# Comin_CTR_v_1_0.net
KiCad netlist of a schematic drawn in EAGLE
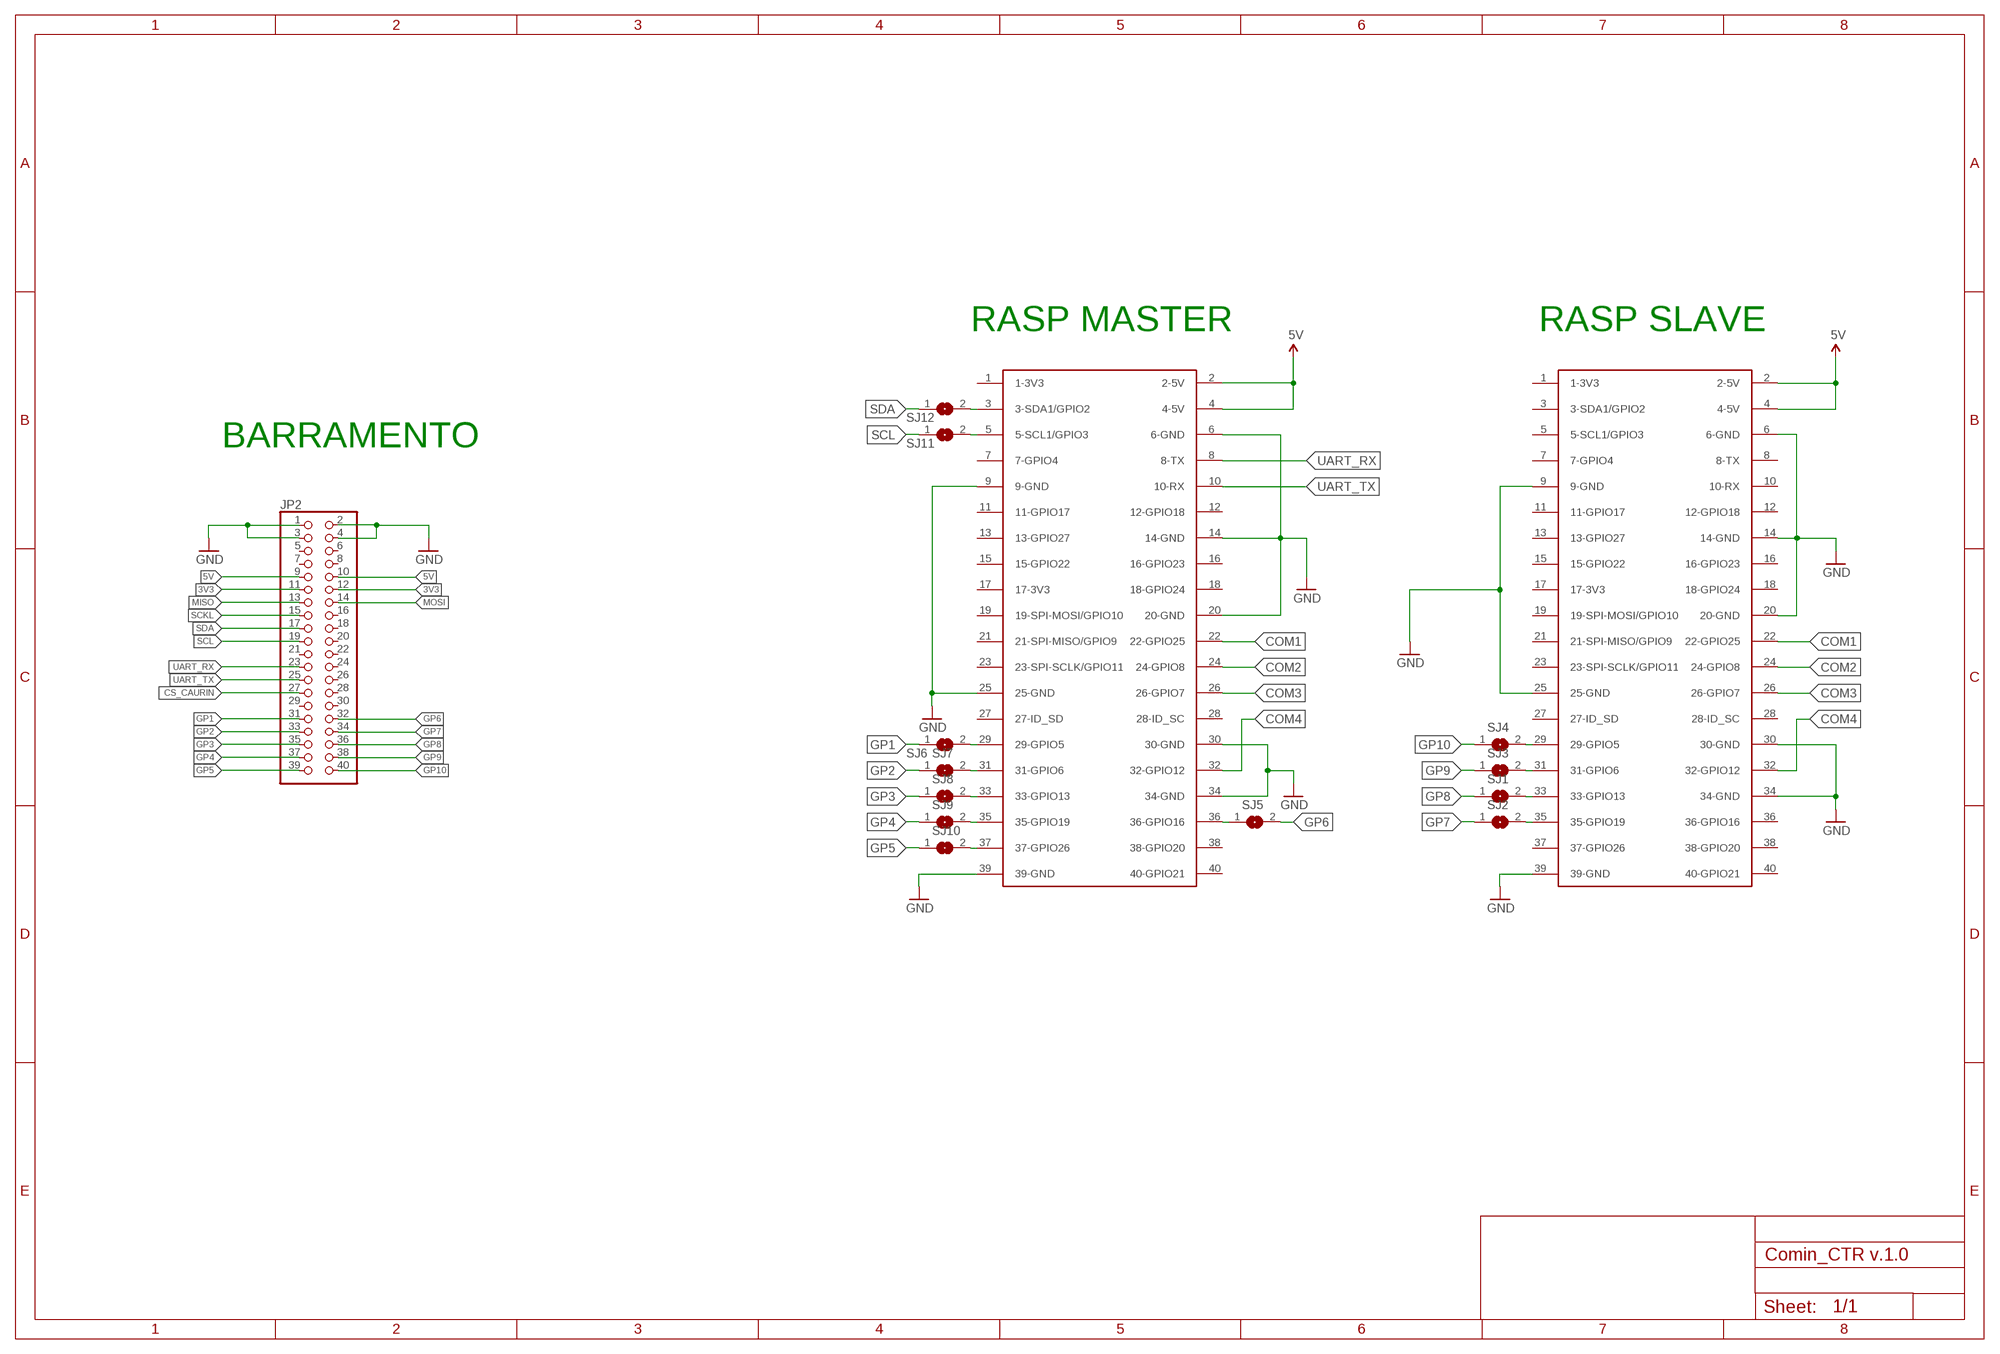
[diagram p0: schematic, sheet 1]

(export (version "E")
  (design (tool "Eeschema 10.0.6"))
  (components
    (comp (ref "JP2")
      (value "PINHD-2X20")
      (footprint "eagle-import:2X20")
      (libsource (lib "eagle-import") (part "PINHD-2X20"))
    )
    (comp (ref "SJ1") (value "SJ") (footprint "eagle-import:SJ") (libsource (lib "eagle-import") (part "SJ")))
    (comp (ref "SJ2") (value "SJ") (footprint "eagle-import:SJ") (libsource (lib "eagle-import") (part "SJ")))
    (comp (ref "SJ3") (value "SJ") (footprint "eagle-import:SJ") (libsource (lib "eagle-import") (part "SJ")))
    (comp (ref "SJ4") (value "SJ") (footprint "eagle-import:SJ") (libsource (lib "eagle-import") (part "SJ")))
    (comp (ref "SJ5") (value "SJ") (footprint "eagle-import:SJ") (libsource (lib "eagle-import") (part "SJ")))
    (comp (ref "SJ6") (value "SJ") (footprint "eagle-import:SJ") (libsource (lib "eagle-import") (part "SJ")))
    (comp (ref "SJ7") (value "SJ") (footprint "eagle-import:SJ") (libsource (lib "eagle-import") (part "SJ")))
    (comp (ref "SJ8") (value "SJ") (footprint "eagle-import:SJ") (libsource (lib "eagle-import") (part "SJ")))
    (comp (ref "SJ9") (value "SJ") (footprint "eagle-import:SJ") (libsource (lib "eagle-import") (part "SJ")))
    (comp (ref "SJ10")
      (value "SJ")
      (footprint "eagle-import:SJ")
      (libsource (lib "eagle-import") (part "SJ"))
    )
    (comp (ref "SJ11")
      (value "SJ")
      (footprint "eagle-import:SJ")
      (libsource (lib "eagle-import") (part "SJ"))
    )
    (comp (ref "SJ12")
      (value "SJ")
      (footprint "eagle-import:SJ")
      (libsource (lib "eagle-import") (part "SJ"))
    )
    (comp (ref "U$1")
      (value "RASPBERRY-PI+PIZERO")
      (footprint "eagle-import:RASPBERRY-PI-ZERO")
      (libsource (lib "eagle-import") (part "RASPBERRY-PI+PIZERO"))
    )
    (comp (ref "U$2")
      (value "RASPBERRY-PI+PIZERO")
      (footprint "eagle-import:RASPBERRY-PI-ZERO")
      (libsource (lib "eagle-import") (part "RASPBERRY-PI+PIZERO"))
    )
  )
  (nets
    (net (code "1") (name "3V3") (class "Default")
      (node (ref "JP2") (pin "11") (pinfunction "11_11") (pintype "passive"))
      (node (ref "JP2") (pin "12") (pinfunction "12_12") (pintype "passive"))
    )
    (net (code "2") (name "5V") (class "Default")
      (node (ref "JP2") (pin "10") (pinfunction "10_10") (pintype "passive"))
      (node (ref "JP2") (pin "9") (pinfunction "9_9") (pintype "passive"))
      (node (ref "U$1") (pin "2") (pinfunction "2-5V_2") (pintype "bidirectional"))
      (node (ref "U$1") (pin "4") (pinfunction "4-5V_4") (pintype "bidirectional"))
      (node (ref "U$2") (pin "2") (pinfunction "2-5V_2") (pintype "bidirectional"))
      (node (ref "U$2") (pin "4") (pinfunction "4-5V_4") (pintype "bidirectional"))
    )
    (net (code "3") (name "COM1") (class "Default")
      (node (ref "U$1") (pin "22") (pinfunction "22-GPIO25_22") (pintype "bidirectional"))
      (node (ref "U$2") (pin "22") (pinfunction "22-GPIO25_22") (pintype "bidirectional"))
    )
    (net (code "4") (name "COM2") (class "Default")
      (node (ref "U$1") (pin "24") (pinfunction "24-GPIO8_24") (pintype "bidirectional"))
      (node (ref "U$2") (pin "24") (pinfunction "24-GPIO8_24") (pintype "bidirectional"))
    )
    (net (code "5") (name "COM3") (class "Default")
      (node (ref "U$1") (pin "26") (pinfunction "26-GPIO7_26") (pintype "bidirectional"))
      (node (ref "U$2") (pin "26") (pinfunction "26-GPIO7_26") (pintype "bidirectional"))
    )
    (net (code "6") (name "COM4") (class "Default")
      (node (ref "U$1") (pin "32") (pinfunction "32-GPIO12_32") (pintype "bidirectional"))
      (node (ref "U$2") (pin "32") (pinfunction "32-GPIO12_32") (pintype "bidirectional"))
    )
    (net (code "7") (name "CS_CAURIN") (class "Default")
      (node (ref "JP2") (pin "27") (pinfunction "27_27") (pintype "passive"))
    )
    (net (code "8") (name "GND") (class "Default")
      (node (ref "JP2") (pin "1") (pinfunction "1_1") (pintype "passive"))
      (node (ref "JP2") (pin "2") (pinfunction "2_2") (pintype "passive"))
      (node (ref "JP2") (pin "3") (pinfunction "3_3") (pintype "passive"))
      (node (ref "JP2") (pin "4") (pinfunction "4_4") (pintype "passive"))
      (node (ref "U$1") (pin "14") (pinfunction "14-GND_14") (pintype "bidirectional"))
      (node (ref "U$1") (pin "20") (pinfunction "20-GND_20") (pintype "bidirectional"))
      (node (ref "U$1") (pin "25") (pinfunction "25-GND_25") (pintype "bidirectional"))
      (node (ref "U$1") (pin "30") (pinfunction "30-GND_30") (pintype "bidirectional"))
      (node (ref "U$1") (pin "34") (pinfunction "34-GND_34") (pintype "bidirectional"))
      (node (ref "U$1") (pin "39") (pinfunction "39-GND_39") (pintype "bidirectional"))
      (node (ref "U$1") (pin "6") (pinfunction "6-GND_6") (pintype "bidirectional"))
      (node (ref "U$1") (pin "9") (pinfunction "9-GND_9") (pintype "bidirectional"))
      (node (ref "U$2") (pin "14") (pinfunction "14-GND_14") (pintype "bidirectional"))
      (node (ref "U$2") (pin "20") (pinfunction "20-GND_20") (pintype "bidirectional"))
      (node (ref "U$2") (pin "25") (pinfunction "25-GND_25") (pintype "bidirectional"))
      (node (ref "U$2") (pin "30") (pinfunction "30-GND_30") (pintype "bidirectional"))
      (node (ref "U$2") (pin "34") (pinfunction "34-GND_34") (pintype "bidirectional"))
      (node (ref "U$2") (pin "39") (pinfunction "39-GND_39") (pintype "bidirectional"))
      (node (ref "U$2") (pin "6") (pinfunction "6-GND_6") (pintype "bidirectional"))
      (node (ref "U$2") (pin "9") (pinfunction "9-GND_9") (pintype "bidirectional"))
    )
    (net (code "9") (name "GP1") (class "Default")
      (node (ref "JP2") (pin "31") (pinfunction "31_31") (pintype "passive"))
      (node (ref "SJ6") (pin "1") (pinfunction "1_1") (pintype "passive"))
    )
    (net (code "10") (name "GP2") (class "Default")
      (node (ref "JP2") (pin "33") (pinfunction "33_33") (pintype "passive"))
      (node (ref "SJ7") (pin "1") (pinfunction "1_1") (pintype "passive"))
    )
    (net (code "11") (name "GP3") (class "Default")
      (node (ref "JP2") (pin "35") (pinfunction "35_35") (pintype "passive"))
      (node (ref "SJ8") (pin "1") (pinfunction "1_1") (pintype "passive"))
    )
    (net (code "12") (name "GP4") (class "Default")
      (node (ref "JP2") (pin "37") (pinfunction "37_37") (pintype "passive"))
      (node (ref "SJ9") (pin "1") (pinfunction "1_1") (pintype "passive"))
    )
    (net (code "13") (name "GP5") (class "Default")
      (node (ref "JP2") (pin "39") (pinfunction "39_39") (pintype "passive"))
      (node (ref "SJ10") (pin "1") (pinfunction "1_1") (pintype "passive"))
    )
    (net (code "14") (name "GP6") (class "Default")
      (node (ref "JP2") (pin "32") (pinfunction "32_32") (pintype "passive"))
      (node (ref "SJ5") (pin "2") (pinfunction "2_2") (pintype "passive"))
    )
    (net (code "15") (name "GP7") (class "Default")
      (node (ref "JP2") (pin "34") (pinfunction "34_34") (pintype "passive"))
      (node (ref "SJ2") (pin "1") (pinfunction "1_1") (pintype "passive"))
    )
    (net (code "16") (name "GP8") (class "Default")
      (node (ref "JP2") (pin "36") (pinfunction "36_36") (pintype "passive"))
      (node (ref "SJ1") (pin "1") (pinfunction "1_1") (pintype "passive"))
    )
    (net (code "17") (name "GP9") (class "Default")
      (node (ref "JP2") (pin "38") (pinfunction "38_38") (pintype "passive"))
      (node (ref "SJ3") (pin "1") (pinfunction "1_1") (pintype "passive"))
    )
    (net (code "18") (name "GP10") (class "Default")
      (node (ref "JP2") (pin "40") (pinfunction "40_40") (pintype "passive"))
      (node (ref "SJ4") (pin "1") (pinfunction "1_1") (pintype "passive"))
    )
    (net (code "19") (name "MISO") (class "Default")
      (node (ref "JP2") (pin "13") (pinfunction "13_13") (pintype "passive"))
    )
    (net (code "20") (name "MOSI") (class "Default")
      (node (ref "JP2") (pin "14") (pinfunction "14_14") (pintype "passive"))
    )
    (net (code "21") (name "Net-(U$1-29-GPIO5)") (class "Default")
      (node (ref "SJ4") (pin "2") (pinfunction "2_2") (pintype "passive"))
      (node (ref "U$1") (pin "29") (pinfunction "29-GPIO5_29") (pintype "bidirectional"))
    )
    (net (code "22") (name "Net-(U$1-31-GPIO6)") (class "Default")
      (node (ref "SJ3") (pin "2") (pinfunction "2_2") (pintype "passive"))
      (node (ref "U$1") (pin "31") (pinfunction "31-GPIO6_31") (pintype "bidirectional"))
    )
    (net (code "23") (name "Net-(U$1-33-GPIO13)") (class "Default")
      (node (ref "SJ1") (pin "2") (pinfunction "2_2") (pintype "passive"))
      (node (ref "U$1") (pin "33") (pinfunction "33-GPIO13_33") (pintype "bidirectional"))
    )
    (net (code "24") (name "Net-(U$1-35-GPIO19)") (class "Default")
      (node (ref "SJ2") (pin "2") (pinfunction "2_2") (pintype "passive"))
      (node (ref "U$1") (pin "35") (pinfunction "35-GPIO19_35") (pintype "bidirectional"))
    )
    (net (code "25") (name "Net-(U$2-3-SDA1{slash}GPIO2)") (class "Default")
      (node (ref "SJ12") (pin "2") (pinfunction "2_2") (pintype "passive"))
      (node (ref "U$2") (pin "3") (pinfunction "3-SDA1/GPIO2_3") (pintype "bidirectional"))
    )
    (net (code "26") (name "Net-(U$2-5-SCL1{slash}GPIO3)") (class "Default")
      (node (ref "SJ11") (pin "2") (pinfunction "2_2") (pintype "passive"))
      (node (ref "U$2") (pin "5") (pinfunction "5-SCL1/GPIO3_5") (pintype "bidirectional"))
    )
    (net (code "27") (name "Net-(U$2-29-GPIO5)") (class "Default")
      (node (ref "SJ6") (pin "2") (pinfunction "2_2") (pintype "passive"))
      (node (ref "U$2") (pin "29") (pinfunction "29-GPIO5_29") (pintype "bidirectional"))
    )
    (net (code "28") (name "Net-(U$2-31-GPIO6)") (class "Default")
      (node (ref "SJ7") (pin "2") (pinfunction "2_2") (pintype "passive"))
      (node (ref "U$2") (pin "31") (pinfunction "31-GPIO6_31") (pintype "bidirectional"))
    )
    (net (code "29") (name "Net-(U$2-33-GPIO13)") (class "Default")
      (node (ref "SJ8") (pin "2") (pinfunction "2_2") (pintype "passive"))
      (node (ref "U$2") (pin "33") (pinfunction "33-GPIO13_33") (pintype "bidirectional"))
    )
    (net (code "30") (name "Net-(U$2-35-GPIO19)") (class "Default")
      (node (ref "SJ9") (pin "2") (pinfunction "2_2") (pintype "passive"))
      (node (ref "U$2") (pin "35") (pinfunction "35-GPIO19_35") (pintype "bidirectional"))
    )
    (net (code "31") (name "Net-(U$2-36-GPIO16)") (class "Default")
      (node (ref "SJ5") (pin "1") (pinfunction "1_1") (pintype "passive"))
      (node (ref "U$2") (pin "36") (pinfunction "36-GPIO16_36") (pintype "bidirectional"))
    )
    (net (code "32") (name "Net-(U$2-37-GPIO26)") (class "Default")
      (node (ref "SJ10") (pin "2") (pinfunction "2_2") (pintype "passive"))
      (node (ref "U$2") (pin "37") (pinfunction "37-GPIO26_37") (pintype "bidirectional"))
    )
    (net (code "33") (name "SCKL") (class "Default")
      (node (ref "JP2") (pin "15") (pinfunction "15_15") (pintype "passive"))
    )
    (net (code "34") (name "SCL") (class "Default")
      (node (ref "JP2") (pin "19") (pinfunction "19_19") (pintype "passive"))
      (node (ref "SJ11") (pin "1") (pinfunction "1_1") (pintype "passive"))
    )
    (net (code "35") (name "SDA") (class "Default")
      (node (ref "JP2") (pin "17") (pinfunction "17_17") (pintype "passive"))
      (node (ref "SJ12") (pin "1") (pinfunction "1_1") (pintype "passive"))
    )
    (net (code "36") (name "UART_RX") (class "Default")
      (node (ref "JP2") (pin "23") (pinfunction "23_23") (pintype "passive"))
      (node (ref "U$2") (pin "8") (pinfunction "8-TX_8") (pintype "bidirectional"))
    )
    (net (code "37") (name "UART_TX") (class "Default")
      (node (ref "JP2") (pin "25") (pinfunction "25_25") (pintype "passive"))
      (node (ref "U$2") (pin "10") (pinfunction "10-RX_10") (pintype "bidirectional"))
    )
    (net (code "38") (name "unconnected-(JP2-Pad5)") (class "Default")
      (node (ref "JP2") (pin "5") (pinfunction "5_5") (pintype "passive"))
    )
    (net (code "39") (name "unconnected-(JP2-Pad6)") (class "Default")
      (node (ref "JP2") (pin "6") (pinfunction "6_6") (pintype "passive"))
    )
    (net (code "40") (name "unconnected-(JP2-Pad7)") (class "Default")
      (node (ref "JP2") (pin "7") (pinfunction "7_7") (pintype "passive"))
    )
    (net (code "41") (name "unconnected-(JP2-Pad8)") (class "Default")
      (node (ref "JP2") (pin "8") (pinfunction "8_8") (pintype "passive"))
    )
    (net (code "42") (name "unconnected-(JP2-Pad16)") (class "Default")
      (node (ref "JP2") (pin "16") (pinfunction "16_16") (pintype "passive"))
    )
    (net (code "43") (name "unconnected-(JP2-Pad18)") (class "Default")
      (node (ref "JP2") (pin "18") (pinfunction "18_18") (pintype "passive"))
    )
    (net (code "44") (name "unconnected-(JP2-Pad20)") (class "Default")
      (node (ref "JP2") (pin "20") (pinfunction "20_20") (pintype "passive"))
    )
    (net (code "45") (name "unconnected-(JP2-Pad21)") (class "Default")
      (node (ref "JP2") (pin "21") (pinfunction "21_21") (pintype "passive"))
    )
    (net (code "46") (name "unconnected-(JP2-Pad22)") (class "Default")
      (node (ref "JP2") (pin "22") (pinfunction "22_22") (pintype "passive"))
    )
    (net (code "47") (name "unconnected-(JP2-Pad24)") (class "Default")
      (node (ref "JP2") (pin "24") (pinfunction "24_24") (pintype "passive"))
    )
    (net (code "48") (name "unconnected-(JP2-Pad26)") (class "Default")
      (node (ref "JP2") (pin "26") (pinfunction "26_26") (pintype "passive"))
    )
    (net (code "49") (name "unconnected-(JP2-Pad28)") (class "Default")
      (node (ref "JP2") (pin "28") (pinfunction "28_28") (pintype "passive"))
    )
    (net (code "50") (name "unconnected-(JP2-Pad29)") (class "Default")
      (node (ref "JP2") (pin "29") (pinfunction "29_29") (pintype "passive"))
    )
    (net (code "51") (name "unconnected-(JP2-Pad30)") (class "Default")
      (node (ref "JP2") (pin "30") (pinfunction "30_30") (pintype "passive"))
    )
    (net (code "52") (name "unconnected-(U$1-1-3V3-Pad1)") (class "Default")
      (node (ref "U$1") (pin "1") (pinfunction "1-3V3_1") (pintype "bidirectional"))
    )
    (net (code "53") (name "unconnected-(U$1-3-SDA1{slash}GPIO2-Pad3)") (class "Default")
      (node (ref "U$1") (pin "3") (pinfunction "3-SDA1/GPIO2_3") (pintype "bidirectional"))
    )
    (net (code "54") (name "unconnected-(U$1-5-SCL1{slash}GPIO3-Pad5)") (class "Default")
      (node (ref "U$1") (pin "5") (pinfunction "5-SCL1/GPIO3_5") (pintype "bidirectional"))
    )
    (net (code "55") (name "unconnected-(U$1-7-GPIO4-Pad7)") (class "Default")
      (node (ref "U$1") (pin "7") (pinfunction "7-GPIO4_7") (pintype "bidirectional"))
    )
    (net (code "56") (name "unconnected-(U$1-8-TX-Pad8)") (class "Default")
      (node (ref "U$1") (pin "8") (pinfunction "8-TX_8") (pintype "bidirectional"))
    )
    (net (code "57") (name "unconnected-(U$1-10-RX-Pad10)") (class "Default")
      (node (ref "U$1") (pin "10") (pinfunction "10-RX_10") (pintype "bidirectional"))
    )
    (net (code "58") (name "unconnected-(U$1-11-GPIO17-Pad11)") (class "Default")
      (node (ref "U$1") (pin "11") (pinfunction "11-GPIO17_11") (pintype "bidirectional"))
    )
    (net (code "59") (name "unconnected-(U$1-12-GPIO18-Pad12)") (class "Default")
      (node (ref "U$1") (pin "12") (pinfunction "12-GPIO18_12") (pintype "bidirectional"))
    )
    (net (code "60") (name "unconnected-(U$1-13-GPIO27-Pad13)") (class "Default")
      (node (ref "U$1") (pin "13") (pinfunction "13-GPIO27_13") (pintype "bidirectional"))
    )
    (net (code "61") (name "unconnected-(U$1-15-GPIO22-Pad15)") (class "Default")
      (node (ref "U$1") (pin "15") (pinfunction "15-GPIO22_15") (pintype "bidirectional"))
    )
    (net (code "62") (name "unconnected-(U$1-16-GPIO23-Pad16)") (class "Default")
      (node (ref "U$1") (pin "16") (pinfunction "16-GPIO23_16") (pintype "bidirectional"))
    )
    (net (code "63") (name "unconnected-(U$1-17-3V3-Pad17)") (class "Default")
      (node (ref "U$1") (pin "17") (pinfunction "17-3V3_17") (pintype "bidirectional"))
    )
    (net (code "64") (name "unconnected-(U$1-18-GPIO24-Pad18)") (class "Default")
      (node (ref "U$1") (pin "18") (pinfunction "18-GPIO24_18") (pintype "bidirectional"))
    )
    (net (code "65") (name "unconnected-(U$1-19-SPI-MOSI{slash}GPIO10-Pad19)") (class "Default")
      (node (ref "U$1") (pin "19") (pinfunction "19-SPI-MOSI/GPIO10_19") (pintype "bidirectional"))
    )
    (net (code "66") (name "unconnected-(U$1-21-SPI-MISO{slash}GPIO9-Pad21)") (class "Default")
      (node (ref "U$1") (pin "21") (pinfunction "21-SPI-MISO/GPIO9_21") (pintype "bidirectional"))
    )
    (net (code "67") (name "unconnected-(U$1-23-SPI-SCLK{slash}GPIO11-Pad23)") (class "Default")
      (node (ref "U$1") (pin "23") (pinfunction "23-SPI-SCLK/GPIO11_23") (pintype "bidirectional"))
    )
    (net (code "68") (name "unconnected-(U$1-27-ID_SD-Pad27)") (class "Default")
      (node (ref "U$1") (pin "27") (pinfunction "27-ID_SD_27") (pintype "bidirectional"))
    )
    (net (code "69") (name "unconnected-(U$1-28-ID_SC-Pad28)") (class "Default")
      (node (ref "U$1") (pin "28") (pinfunction "28-ID_SC_28") (pintype "bidirectional"))
    )
    (net (code "70") (name "unconnected-(U$1-36-GPIO16-Pad36)") (class "Default")
      (node (ref "U$1") (pin "36") (pinfunction "36-GPIO16_36") (pintype "bidirectional"))
    )
    (net (code "71") (name "unconnected-(U$1-37-GPIO26-Pad37)") (class "Default")
      (node (ref "U$1") (pin "37") (pinfunction "37-GPIO26_37") (pintype "bidirectional"))
    )
    (net (code "72") (name "unconnected-(U$1-38-GPIO20-Pad38)") (class "Default")
      (node (ref "U$1") (pin "38") (pinfunction "38-GPIO20_38") (pintype "bidirectional"))
    )
    (net (code "73") (name "unconnected-(U$1-40-GPIO21-Pad40)") (class "Default")
      (node (ref "U$1") (pin "40") (pinfunction "40-GPIO21_40") (pintype "bidirectional"))
    )
    (net (code "74") (name "unconnected-(U$2-1-3V3-Pad1)") (class "Default")
      (node (ref "U$2") (pin "1") (pinfunction "1-3V3_1") (pintype "bidirectional"))
    )
    (net (code "75") (name "unconnected-(U$2-7-GPIO4-Pad7)") (class "Default")
      (node (ref "U$2") (pin "7") (pinfunction "7-GPIO4_7") (pintype "bidirectional"))
    )
    (net (code "76") (name "unconnected-(U$2-11-GPIO17-Pad11)") (class "Default")
      (node (ref "U$2") (pin "11") (pinfunction "11-GPIO17_11") (pintype "bidirectional"))
    )
    (net (code "77") (name "unconnected-(U$2-12-GPIO18-Pad12)") (class "Default")
      (node (ref "U$2") (pin "12") (pinfunction "12-GPIO18_12") (pintype "bidirectional"))
    )
    (net (code "78") (name "unconnected-(U$2-13-GPIO27-Pad13)") (class "Default")
      (node (ref "U$2") (pin "13") (pinfunction "13-GPIO27_13") (pintype "bidirectional"))
    )
    (net (code "79") (name "unconnected-(U$2-15-GPIO22-Pad15)") (class "Default")
      (node (ref "U$2") (pin "15") (pinfunction "15-GPIO22_15") (pintype "bidirectional"))
    )
    (net (code "80") (name "unconnected-(U$2-16-GPIO23-Pad16)") (class "Default")
      (node (ref "U$2") (pin "16") (pinfunction "16-GPIO23_16") (pintype "bidirectional"))
    )
    (net (code "81") (name "unconnected-(U$2-17-3V3-Pad17)") (class "Default")
      (node (ref "U$2") (pin "17") (pinfunction "17-3V3_17") (pintype "bidirectional"))
    )
    (net (code "82") (name "unconnected-(U$2-18-GPIO24-Pad18)") (class "Default")
      (node (ref "U$2") (pin "18") (pinfunction "18-GPIO24_18") (pintype "bidirectional"))
    )
    (net (code "83") (name "unconnected-(U$2-19-SPI-MOSI{slash}GPIO10-Pad19)") (class "Default")
      (node (ref "U$2") (pin "19") (pinfunction "19-SPI-MOSI/GPIO10_19") (pintype "bidirectional"))
    )
    (net (code "84") (name "unconnected-(U$2-21-SPI-MISO{slash}GPIO9-Pad21)") (class "Default")
      (node (ref "U$2") (pin "21") (pinfunction "21-SPI-MISO/GPIO9_21") (pintype "bidirectional"))
    )
    (net (code "85") (name "unconnected-(U$2-23-SPI-SCLK{slash}GPIO11-Pad23)") (class "Default")
      (node (ref "U$2") (pin "23") (pinfunction "23-SPI-SCLK/GPIO11_23") (pintype "bidirectional"))
    )
    (net (code "86") (name "unconnected-(U$2-27-ID_SD-Pad27)") (class "Default")
      (node (ref "U$2") (pin "27") (pinfunction "27-ID_SD_27") (pintype "bidirectional"))
    )
    (net (code "87") (name "unconnected-(U$2-28-ID_SC-Pad28)") (class "Default")
      (node (ref "U$2") (pin "28") (pinfunction "28-ID_SC_28") (pintype "bidirectional"))
    )
    (net (code "88") (name "unconnected-(U$2-38-GPIO20-Pad38)") (class "Default")
      (node (ref "U$2") (pin "38") (pinfunction "38-GPIO20_38") (pintype "bidirectional"))
    )
    (net (code "89") (name "unconnected-(U$2-40-GPIO21-Pad40)") (class "Default")
      (node (ref "U$2") (pin "40") (pinfunction "40-GPIO21_40") (pintype "bidirectional"))
    )
  )
)
